# -.net
KiCad netlist of a schematic drawn in Altium Designer
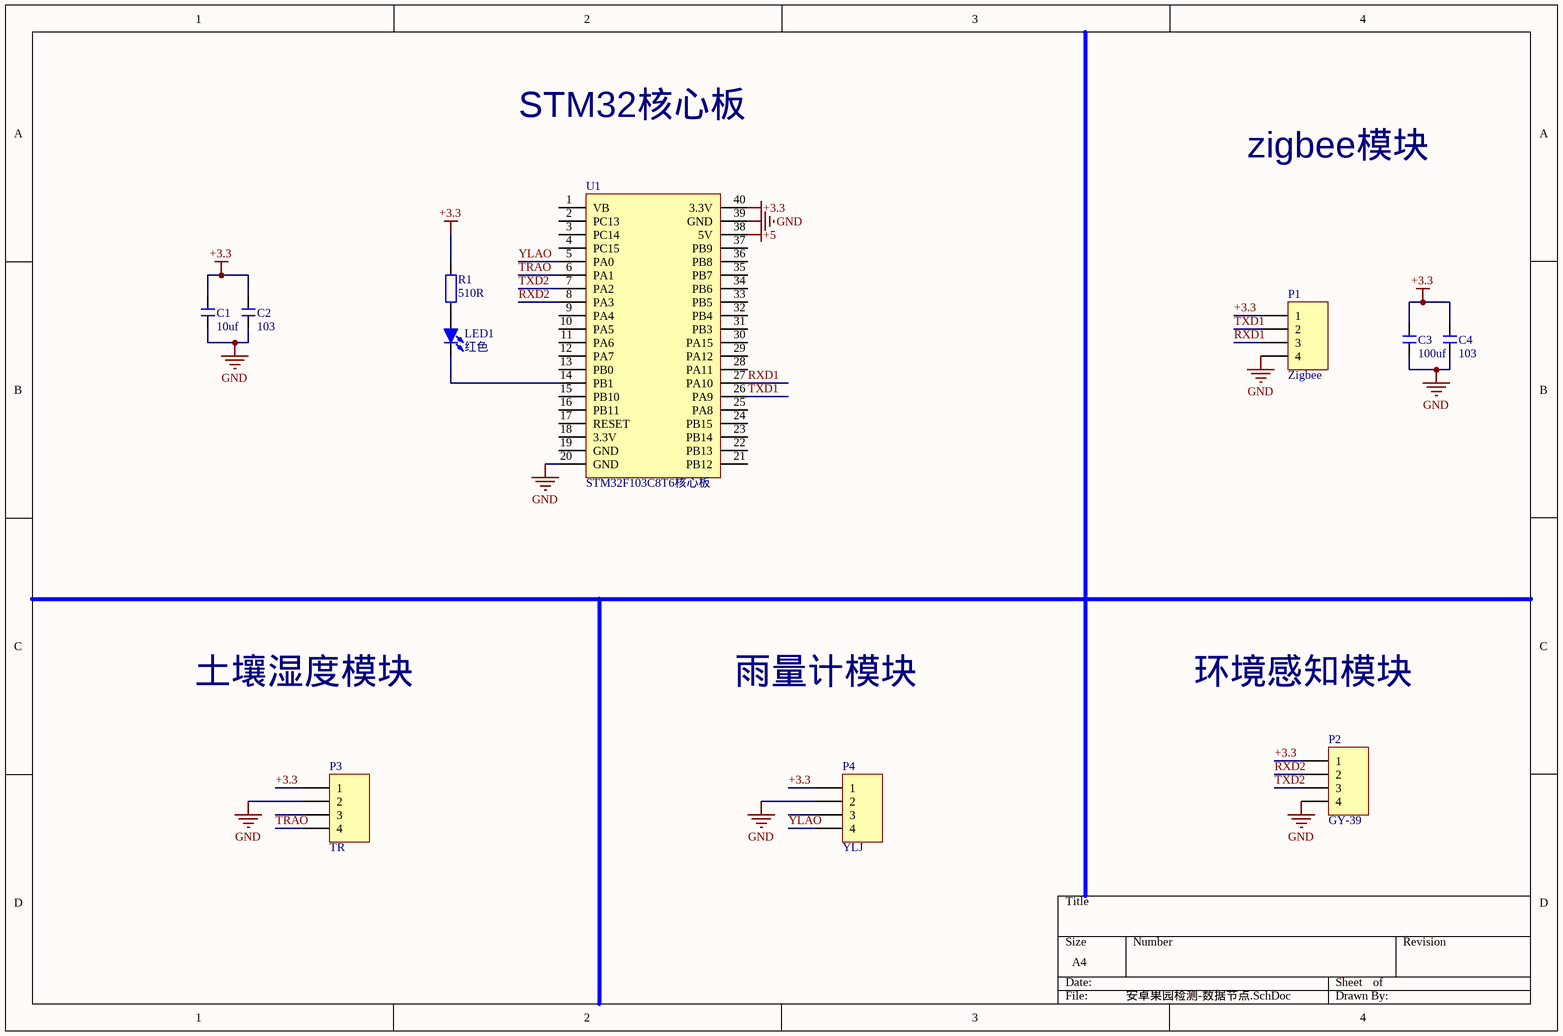
[diagram p0: 安卓果园检测-数据节点.SchDoc]

(export (version "E")
  (design (tool "Eeschema 10.0.6"))
  (components
    (comp (ref "C1")
      (value "10uf")
      (footprint "R 0805_M")
      (description "直插瓷片电容")
      (fields (field (name "版权归属") "源创客"))
      (libsource (lib "3.1   - 电阻-电容-电感") (part "C-CC"))
    )
    (comp (ref "C2")
      (value "103")
      (footprint "R 0805_M")
      (description "直插瓷片电容")
      (fields (field (name "版权归属") "源创客"))
      (libsource (lib "3.1   - 电阻-电容-电感") (part "C-CC"))
    )
    (comp (ref "C3")
      (value "100uf")
      (footprint "R 0805_M")
      (description "直插瓷片电容")
      (fields (field (name "版权归属") "源创客"))
      (libsource (lib "3.1   - 电阻-电容-电感") (part "C-CC"))
    )
    (comp (ref "C4")
      (value "103")
      (footprint "R 0805_M")
      (description "直插瓷片电容")
      (fields (field (name "版权归属") "源创客"))
      (libsource (lib "3.1   - 电阻-电容-电感") (part "C-CC"))
    )
    (comp (ref "LED1")
      (value "红色")
      (footprint "LED 0805R")
      (description "贴片LED")
      (fields (field (name "版权归属") "源创客"))
      (libsource (lib "9.1   - LED") (part "LED-SMD"))
    )
    (comp (ref "P1")
      (value "Zigbee")
      (footprint "HDR1X4")
      (description "Header, 4-Pin")
      (fields (field (name "PUBLISHER") "Altium Limited"))
      (libsource (lib "Miscellaneous Connectors") (part "Header 4"))
    )
    (comp (ref "P2")
      (value "GY-39")
      (footprint "HDR1X4")
      (description "Header, 4-Pin")
      (fields (field (name "PUBLISHER") "Altium Limited"))
      (libsource (lib "Miscellaneous Connectors") (part "Header 4"))
    )
    (comp (ref "P3")
      (value "TR")
      (footprint "HDR1X4")
      (description "Header, 4-Pin")
      (fields (field (name "PUBLISHER") "Altium Limited"))
      (libsource (lib "Miscellaneous Connectors") (part "Header 4"))
    )
    (comp (ref "P4")
      (value "YLJ")
      (footprint "HDR1X4")
      (description "Header, 4-Pin")
      (fields (field (name "PUBLISHER") "Altium Limited"))
      (libsource (lib "Miscellaneous Connectors") (part "Header 4"))
    )
    (comp (ref "R1")
      (value "510R")
      (footprint "R 0805_M")
      (description "直插色环电阻")
      (fields (field (name "版权归属") "源创客"))
      (libsource (lib "3.1   - 电阻-电容-电感") (part "R-CRR"))
    )
    (comp (ref "U1")
      (value "STM32F103C8T6核心板")
      (footprint "DIP40-600_MH")
      (libsource (lib "STM32F103C8T6核心板") (part "STM32F103C8T6核心板"))
    )
  )
  (nets
    (net (code "1") (name "+3.3") (class "Default")
      (node (ref "C1") (pin "1") (pinfunction "1_1") (pintype "passive"))
      (node (ref "C2") (pin "1") (pinfunction "1_1") (pintype "passive"))
      (node (ref "C3") (pin "1") (pinfunction "1_1") (pintype "passive"))
      (node (ref "C4") (pin "1") (pinfunction "1_1") (pintype "passive"))
      (node (ref "P1") (pin "1") (pinfunction "1_1") (pintype "passive"))
      (node (ref "P2") (pin "1") (pinfunction "1_1") (pintype "passive"))
      (node (ref "P3") (pin "1") (pinfunction "1_1") (pintype "passive"))
      (node (ref "P4") (pin "1") (pinfunction "1_1") (pintype "passive"))
      (node (ref "R1") (pin "2") (pinfunction "2_2") (pintype "passive"))
      (node (ref "U1") (pin "40") (pinfunction "3.3V_40") (pintype "passive"))
    )
    (net (code "2") (name "+5") (class "Default")
      (node (ref "U1") (pin "38") (pinfunction "5V_38") (pintype "passive"))
    )
    (net (code "3") (name "/RXD1") (class "Default")
      (node (ref "P1") (pin "3") (pinfunction "3_3") (pintype "passive"))
      (node (ref "U1") (pin "27") (pinfunction "PA10_27") (pintype "passive"))
    )
    (net (code "4") (name "/RXD2") (class "Default")
      (node (ref "P2") (pin "2") (pinfunction "2_2") (pintype "passive"))
      (node (ref "U1") (pin "8") (pinfunction "PA3_8") (pintype "passive"))
    )
    (net (code "5") (name "/TRAO") (class "Default")
      (node (ref "P3") (pin "4") (pinfunction "4_4") (pintype "passive"))
      (node (ref "U1") (pin "6") (pinfunction "PA1_6") (pintype "passive"))
    )
    (net (code "6") (name "/TXD1") (class "Default")
      (node (ref "P1") (pin "2") (pinfunction "2_2") (pintype "passive"))
      (node (ref "U1") (pin "26") (pinfunction "PA9_26") (pintype "passive"))
    )
    (net (code "7") (name "/TXD2") (class "Default")
      (node (ref "P2") (pin "3") (pinfunction "3_3") (pintype "passive"))
      (node (ref "U1") (pin "7") (pinfunction "PA2_7") (pintype "passive"))
    )
    (net (code "8") (name "/YLAO") (class "Default")
      (node (ref "P4") (pin "4") (pinfunction "4_4") (pintype "passive"))
      (node (ref "U1") (pin "5") (pinfunction "PA0_5") (pintype "passive"))
    )
    (net (code "9") (name "GND") (class "Default")
      (node (ref "C1") (pin "2") (pinfunction "2_2") (pintype "passive"))
      (node (ref "C2") (pin "2") (pinfunction "2_2") (pintype "passive"))
      (node (ref "C3") (pin "2") (pinfunction "2_2") (pintype "passive"))
      (node (ref "C4") (pin "2") (pinfunction "2_2") (pintype "passive"))
      (node (ref "P1") (pin "4") (pinfunction "4_4") (pintype "passive"))
      (node (ref "P2") (pin "4") (pinfunction "4_4") (pintype "passive"))
      (node (ref "P3") (pin "2") (pinfunction "2_2") (pintype "passive"))
      (node (ref "P4") (pin "2") (pinfunction "2_2") (pintype "passive"))
      (node (ref "U1") (pin "20") (pinfunction "GND_20") (pintype "passive"))
      (node (ref "U1") (pin "39") (pinfunction "GND_39") (pintype "passive"))
    )
    (net (code "10") (name "Net-(LED1-A)") (class "Default")
      (node (ref "LED1") (pin "1") (pinfunction "A_1") (pintype "passive"))
      (node (ref "R1") (pin "1") (pinfunction "1_1") (pintype "passive"))
    )
    (net (code "11") (name "Net-(LED1-K)") (class "Default")
      (node (ref "LED1") (pin "2") (pinfunction "K_2") (pintype "passive"))
      (node (ref "U1") (pin "14") (pinfunction "PB1_14") (pintype "passive"))
    )
    (net (code "12") (name "unconnected-(P3-Pad3)") (class "Default")
      (node (ref "P3") (pin "3") (pinfunction "3_3") (pintype "passive"))
    )
    (net (code "13") (name "unconnected-(P4-Pad3)") (class "Default")
      (node (ref "P4") (pin "3") (pinfunction "3_3") (pintype "passive"))
    )
    (net (code "14") (name "unconnected-(U1-3.3V-Pad18)") (class "Default")
      (node (ref "U1") (pin "18") (pinfunction "3.3V_18") (pintype "passive"))
    )
    (net (code "15") (name "unconnected-(U1-GND-Pad19)") (class "Default")
      (node (ref "U1") (pin "19") (pinfunction "GND_19") (pintype "passive"))
    )
    (net (code "16") (name "unconnected-(U1-PA4-Pad9)") (class "Default")
      (node (ref "U1") (pin "9") (pinfunction "PA4_9") (pintype "passive"))
    )
    (net (code "17") (name "unconnected-(U1-PA5-Pad10)") (class "Default")
      (node (ref "U1") (pin "10") (pinfunction "PA5_10") (pintype "passive"))
    )
    (net (code "18") (name "unconnected-(U1-PA6-Pad11)") (class "Default")
      (node (ref "U1") (pin "11") (pinfunction "PA6_11") (pintype "passive"))
    )
    (net (code "19") (name "unconnected-(U1-PA7-Pad12)") (class "Default")
      (node (ref "U1") (pin "12") (pinfunction "PA7_12") (pintype "passive"))
    )
    (net (code "20") (name "unconnected-(U1-PA8-Pad25)") (class "Default")
      (node (ref "U1") (pin "25") (pinfunction "PA8_25") (pintype "passive"))
    )
    (net (code "21") (name "unconnected-(U1-PA11-Pad28)") (class "Default")
      (node (ref "U1") (pin "28") (pinfunction "PA11_28") (pintype "passive"))
    )
    (net (code "22") (name "unconnected-(U1-PA12-Pad29)") (class "Default")
      (node (ref "U1") (pin "29") (pinfunction "PA12_29") (pintype "passive"))
    )
    (net (code "23") (name "unconnected-(U1-PA15-Pad30)") (class "Default")
      (node (ref "U1") (pin "30") (pinfunction "PA15_30") (pintype "passive"))
    )
    (net (code "24") (name "unconnected-(U1-PB0-Pad13)") (class "Default")
      (node (ref "U1") (pin "13") (pinfunction "PB0_13") (pintype "passive"))
    )
    (net (code "25") (name "unconnected-(U1-PB3-Pad31)") (class "Default")
      (node (ref "U1") (pin "31") (pinfunction "PB3_31") (pintype "passive"))
    )
    (net (code "26") (name "unconnected-(U1-PB4-Pad32)") (class "Default")
      (node (ref "U1") (pin "32") (pinfunction "PB4_32") (pintype "passive"))
    )
    (net (code "27") (name "unconnected-(U1-PB5-Pad33)") (class "Default")
      (node (ref "U1") (pin "33") (pinfunction "PB5_33") (pintype "passive"))
    )
    (net (code "28") (name "unconnected-(U1-PB6-Pad34)") (class "Default")
      (node (ref "U1") (pin "34") (pinfunction "PB6_34") (pintype "passive"))
    )
    (net (code "29") (name "unconnected-(U1-PB7-Pad35)") (class "Default")
      (node (ref "U1") (pin "35") (pinfunction "PB7_35") (pintype "passive"))
    )
    (net (code "30") (name "unconnected-(U1-PB8-Pad36)") (class "Default")
      (node (ref "U1") (pin "36") (pinfunction "PB8_36") (pintype "passive"))
    )
    (net (code "31") (name "unconnected-(U1-PB9-Pad37)") (class "Default")
      (node (ref "U1") (pin "37") (pinfunction "PB9_37") (pintype "passive"))
    )
    (net (code "32") (name "unconnected-(U1-PB10-Pad15)") (class "Default")
      (node (ref "U1") (pin "15") (pinfunction "PB10_15") (pintype "passive"))
    )
    (net (code "33") (name "unconnected-(U1-PB11-Pad16)") (class "Default")
      (node (ref "U1") (pin "16") (pinfunction "PB11_16") (pintype "passive"))
    )
    (net (code "34") (name "unconnected-(U1-PB12-Pad21)") (class "Default")
      (node (ref "U1") (pin "21") (pinfunction "PB12_21") (pintype "passive"))
    )
    (net (code "35") (name "unconnected-(U1-PB13-Pad22)") (class "Default")
      (node (ref "U1") (pin "22") (pinfunction "PB13_22") (pintype "passive"))
    )
    (net (code "36") (name "unconnected-(U1-PB14-Pad23)") (class "Default")
      (node (ref "U1") (pin "23") (pinfunction "PB14_23") (pintype "passive"))
    )
    (net (code "37") (name "unconnected-(U1-PB15-Pad24)") (class "Default")
      (node (ref "U1") (pin "24") (pinfunction "PB15_24") (pintype "passive"))
    )
    (net (code "38") (name "unconnected-(U1-PC13-Pad2)") (class "Default")
      (node (ref "U1") (pin "2") (pinfunction "PC13_2") (pintype "passive"))
    )
    (net (code "39") (name "unconnected-(U1-PC14-Pad3)") (class "Default")
      (node (ref "U1") (pin "3") (pinfunction "PC14_3") (pintype "passive"))
    )
    (net (code "40") (name "unconnected-(U1-PC15-Pad4)") (class "Default")
      (node (ref "U1") (pin "4") (pinfunction "PC15_4") (pintype "passive"))
    )
    (net (code "41") (name "unconnected-(U1-RESET-Pad17)") (class "Default")
      (node (ref "U1") (pin "17") (pinfunction "RESET_17") (pintype "passive"))
    )
    (net (code "42") (name "unconnected-(U1-VB-Pad1)") (class "Default")
      (node (ref "U1") (pin "1") (pinfunction "VB_1") (pintype "passive"))
    )
  )
)
